# latch_THT.net
KiCad netlist of a schematic drawn in EAGLE
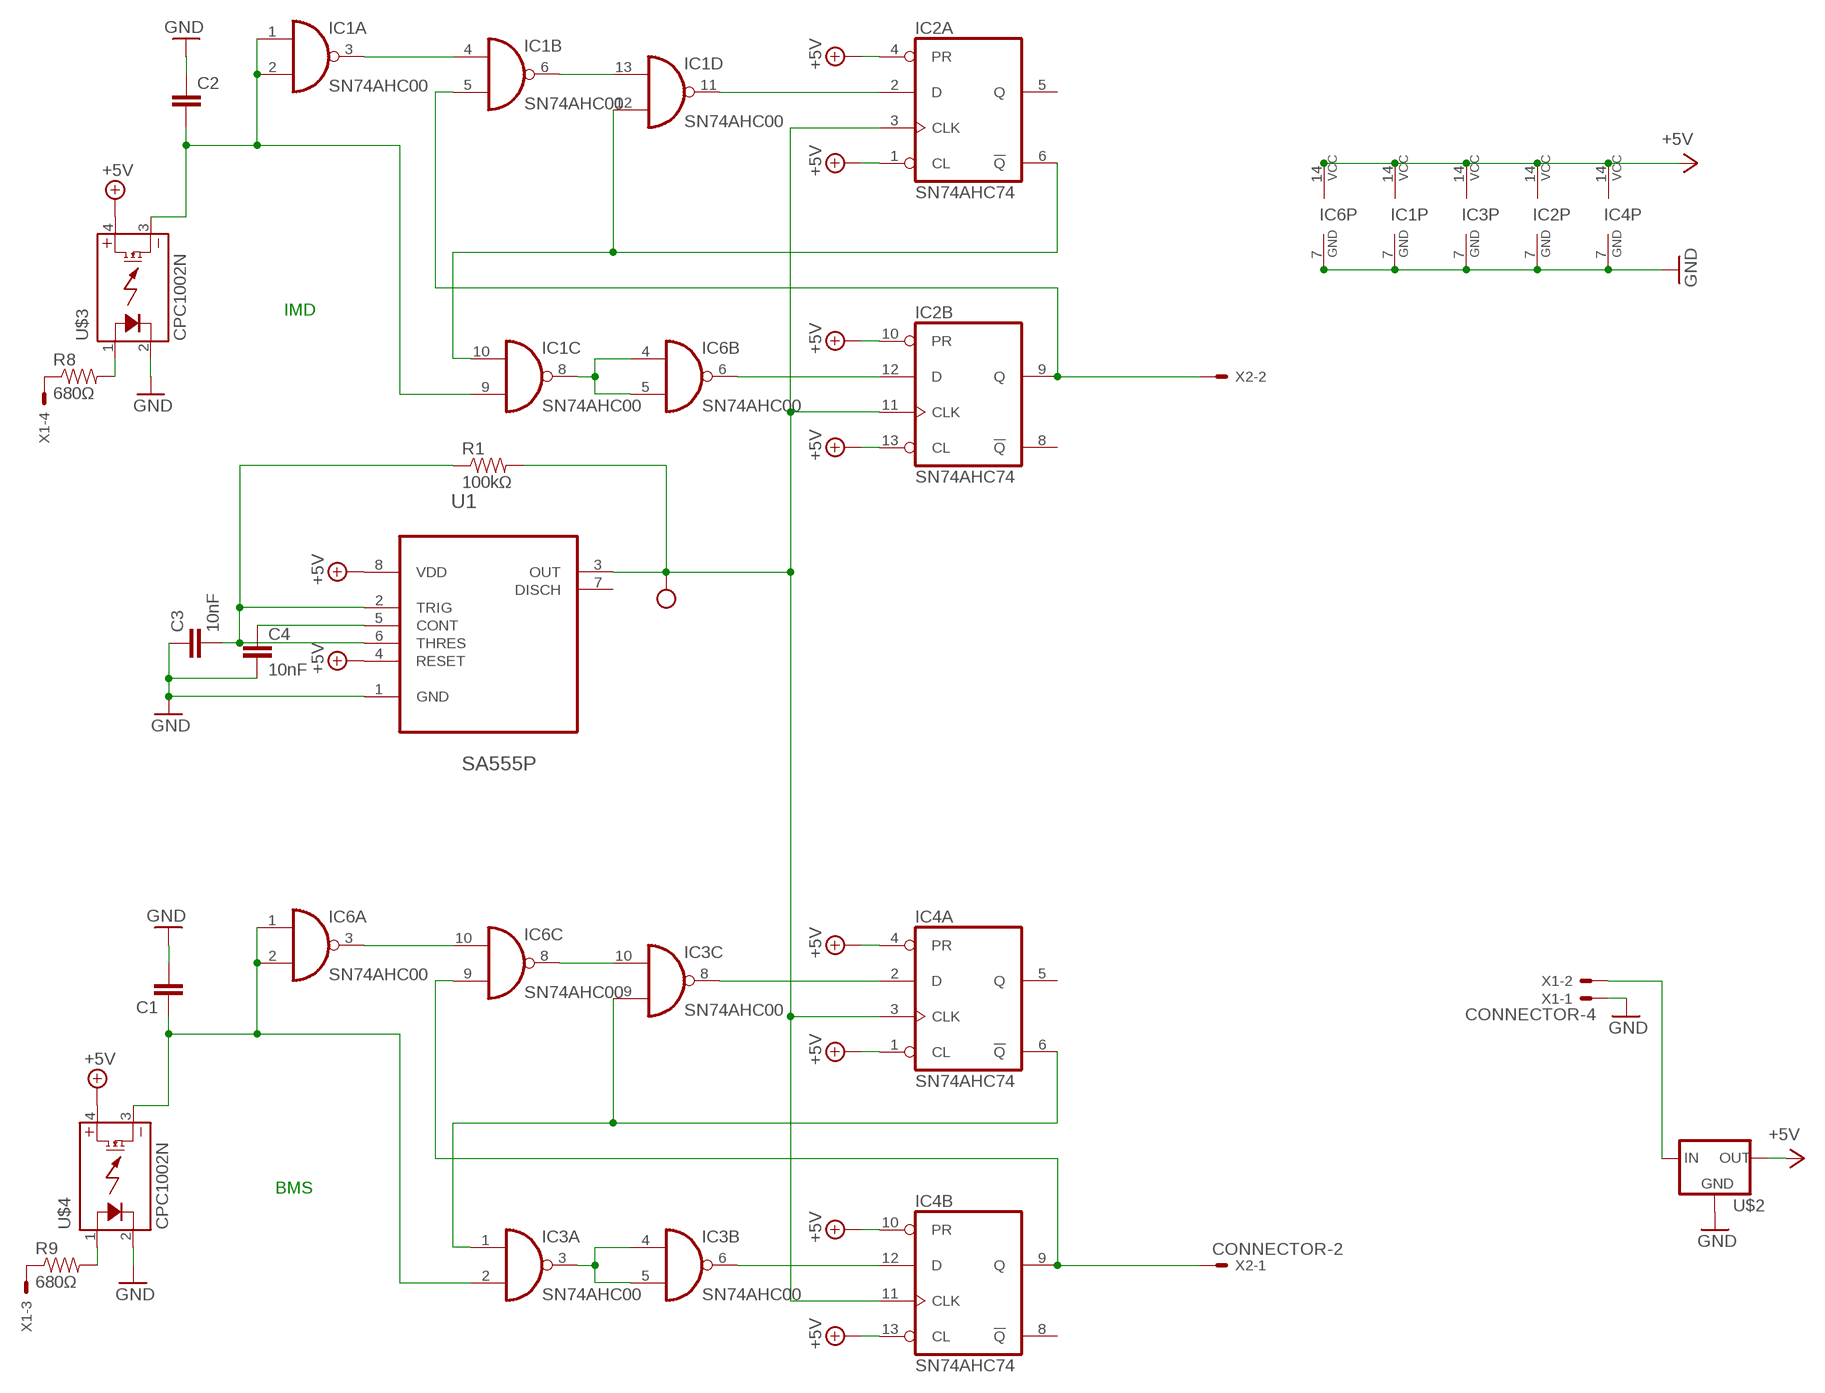
[diagram p0: schematic, sheet 1]

(export (version "E")
  (design (tool "Eeschema 10.0.6"))
  (components
    (comp (ref "C1")
      (value "CAP_")
      (footprint "eagle-import:AXIAL-5MM")
      (libsource (lib "eagle-import") (part "CAP_"))
    )
    (comp (ref "C2")
      (value "CAP_")
      (footprint "eagle-import:AXIAL-5MM")
      (libsource (lib "eagle-import") (part "CAP_"))
    )
    (comp (ref "C3")
      (value "10nF")
      (footprint "eagle-import:AXIAL-5MM")
      (libsource (lib "eagle-import") (part "CAP_"))
    )
    (comp (ref "C4")
      (value "10nF")
      (footprint "eagle-import:AXIAL-5MM")
      (libsource (lib "eagle-import") (part "CAP_"))
    )
    (comp (ref "IC1")
      (value "SN74AHC00")
      (footprint "eagle-import:DIL14")
      (libsource (lib "eagle-import") (part "SN74AHC00"))
    )
    (comp (ref "IC2")
      (value "SN74AHC74")
      (footprint "eagle-import:DIL14")
      (libsource (lib "eagle-import") (part "SN74AHC74"))
    )
    (comp (ref "IC3")
      (value "SN74AHC00")
      (footprint "eagle-import:DIL14")
      (libsource (lib "eagle-import") (part "SN74AHC00"))
    )
    (comp (ref "IC4")
      (value "SN74AHC74")
      (footprint "eagle-import:DIL14")
      (libsource (lib "eagle-import") (part "SN74AHC74"))
    )
    (comp (ref "IC6")
      (value "SN74AHC00")
      (footprint "eagle-import:DIL14")
      (libsource (lib "eagle-import") (part "SN74AHC00"))
    )
    (comp (ref "R1")
      (value "100kΩ")
      (footprint "eagle-import:AXIAL-0.4")
      (libsource (lib "eagle-import") (part "RESISTORPTH-1/4W"))
    )
    (comp (ref "R8")
      (value "680Ω")
      (footprint "eagle-import:AXIAL-0.4")
      (libsource (lib "eagle-import") (part "RESISTORPTH-1/4W"))
    )
    (comp (ref "R9")
      (value "680Ω")
      (footprint "eagle-import:AXIAL-0.4")
      (libsource (lib "eagle-import") (part "RESISTORPTH-1/4W"))
    )
    (comp (ref "U$1")
      (value "TEST_POINT")
      (footprint "eagle-import:TEST_POINT")
      (libsource (lib "eagle-import") (part "TEST_POINT"))
    )
    (comp (ref "U$2")
      (value "5VREG_LM340-NLM340T-5.0/NOPB")
      (footprint "eagle-import:TO-220")
      (libsource (lib "eagle-import") (part "5VREG_LM340-NLM340T-5.0/NOPB"))
    )
    (comp (ref "U$3")
      (value "CPC1002N")
      (footprint "eagle-import:SOP04")
      (libsource (lib "eagle-import") (part "CPC1002N"))
    )
    (comp (ref "U$4")
      (value "CPC1002N")
      (footprint "eagle-import:SOP04")
      (libsource (lib "eagle-import") (part "CPC1002N"))
    )
    (comp (ref "U1")
      (value "SA555P")
      (footprint "eagle-import:DIP254P762X508-8")
      (libsource (lib "eagle-import") (part "SA555P"))
    )
    (comp (ref "X1")
      (value "CONNECTOR-4")
      (footprint "eagle-import:MINIFIT_5566-4")
      (libsource (lib "eagle-import") (part "CONNECTOR-4"))
    )
    (comp (ref "X2")
      (value "CONNECTOR-2")
      (footprint "eagle-import:MINIFIT_5566-2")
      (libsource (lib "eagle-import") (part "CONNECTOR-2"))
    )
  )
  (nets
    (net (code "1") (name "+5V") (class "Default")
      (node (ref "IC1") (pin "14") (pinfunction "VCC_14") (pintype "power_in"))
      (node (ref "IC2") (pin "1") (pinfunction "CL_1") (pintype "input"))
      (node (ref "IC2") (pin "10") (pinfunction "PR_10") (pintype "input"))
      (node (ref "IC2") (pin "13") (pinfunction "CL_13") (pintype "input"))
      (node (ref "IC2") (pin "14") (pinfunction "VCC_14") (pintype "power_in"))
      (node (ref "IC2") (pin "4") (pinfunction "PR_4") (pintype "input"))
      (node (ref "IC3") (pin "14") (pinfunction "VCC_14") (pintype "power_in"))
      (node (ref "IC4") (pin "1") (pinfunction "CL_1") (pintype "input"))
      (node (ref "IC4") (pin "10") (pinfunction "PR_10") (pintype "input"))
      (node (ref "IC4") (pin "13") (pinfunction "CL_13") (pintype "input"))
      (node (ref "IC4") (pin "14") (pinfunction "VCC_14") (pintype "power_in"))
      (node (ref "IC4") (pin "4") (pinfunction "PR_4") (pintype "input"))
      (node (ref "IC6") (pin "14") (pinfunction "VCC_14") (pintype "power_in"))
      (node (ref "U$2") (pin "3") (pinfunction "OUT_3") (pintype "output"))
      (node (ref "U$3") (pin "4") (pinfunction "DC+_4") (pintype "passive"))
      (node (ref "U$4") (pin "4") (pinfunction "DC+_4") (pintype "passive"))
      (node (ref "U1") (pin "4") (pinfunction "RESET_4") (pintype "input"))
      (node (ref "U1") (pin "8") (pinfunction "VDD_8") (pintype "power_in"))
    )
    (net (code "2") (name "GND") (class "Default")
      (node (ref "C1") (pin "P$2") (pinfunction "2_P$2") (pintype "passive"))
      (node (ref "C2") (pin "P$1") (pinfunction "1_P$1") (pintype "passive"))
      (node (ref "C3") (pin "P$1") (pinfunction "1_P$1") (pintype "passive"))
      (node (ref "C4") (pin "P$2") (pinfunction "2_P$2") (pintype "passive"))
      (node (ref "IC1") (pin "7") (pinfunction "GND_7") (pintype "power_in"))
      (node (ref "IC2") (pin "7") (pinfunction "GND_7") (pintype "power_in"))
      (node (ref "IC3") (pin "7") (pinfunction "GND_7") (pintype "power_in"))
      (node (ref "IC4") (pin "7") (pinfunction "GND_7") (pintype "power_in"))
      (node (ref "IC6") (pin "7") (pinfunction "GND_7") (pintype "power_in"))
      (node (ref "U$2") (pin "2") (pinfunction "GND_2") (pintype "input"))
      (node (ref "U$3") (pin "2") (pinfunction "CONTROL-_2") (pintype "passive"))
      (node (ref "U$4") (pin "2") (pinfunction "CONTROL-_2") (pintype "passive"))
      (node (ref "U1") (pin "1") (pinfunction "GND_1") (pintype "passive"))
      (node (ref "X1") (pin "1") (pinfunction "S_1") (pintype "passive"))
    )
    (net (code "3") (name "Net-(C1-1)") (class "Default")
      (node (ref "C1") (pin "P$1") (pinfunction "1_P$1") (pintype "passive"))
      (node (ref "IC3") (pin "2") (pinfunction "I1_2") (pintype "input"))
      (node (ref "IC6") (pin "1") (pinfunction "I0_1") (pintype "input"))
      (node (ref "IC6") (pin "2") (pinfunction "I1_2") (pintype "input"))
      (node (ref "U$4") (pin "3") (pinfunction "DC-_3") (pintype "passive"))
    )
    (net (code "4") (name "Net-(C2-2)") (class "Default")
      (node (ref "C2") (pin "P$2") (pinfunction "2_P$2") (pintype "passive"))
      (node (ref "IC1") (pin "1") (pinfunction "I0_1") (pintype "input"))
      (node (ref "IC1") (pin "2") (pinfunction "I1_2") (pintype "input"))
      (node (ref "IC1") (pin "9") (pinfunction "I1_9") (pintype "input"))
      (node (ref "U$3") (pin "3") (pinfunction "DC-_3") (pintype "passive"))
    )
    (net (code "5") (name "Net-(C3-2)") (class "Default")
      (node (ref "C3") (pin "P$2") (pinfunction "2_P$2") (pintype "passive"))
      (node (ref "R1") (pin "P$1") (pinfunction "1_P$1") (pintype "passive"))
      (node (ref "U1") (pin "2") (pinfunction "TRIG_2") (pintype "input"))
      (node (ref "U1") (pin "6") (pinfunction "THRES_6") (pintype "input"))
    )
    (net (code "6") (name "Net-(C4-1)") (class "Default")
      (node (ref "C4") (pin "P$1") (pinfunction "1_P$1") (pintype "passive"))
      (node (ref "U1") (pin "5") (pinfunction "CONT_5") (pintype "input"))
    )
    (net (code "7") (name "Net-(IC1A-O)") (class "Default")
      (node (ref "IC1") (pin "3") (pinfunction "O_3") (pintype "output"))
      (node (ref "IC1") (pin "4") (pinfunction "I0_4") (pintype "input"))
    )
    (net (code "8") (name "Net-(IC1B-I1)") (class "Default")
      (node (ref "IC1") (pin "5") (pinfunction "I1_5") (pintype "input"))
      (node (ref "IC2") (pin "9") (pinfunction "Q_9") (pintype "output"))
      (node (ref "X2") (pin "2") (pinfunction "S_2") (pintype "passive"))
    )
    (net (code "9") (name "Net-(IC1B-O)") (class "Default")
      (node (ref "IC1") (pin "13") (pinfunction "I0_13") (pintype "input"))
      (node (ref "IC1") (pin "6") (pinfunction "O_6") (pintype "output"))
    )
    (net (code "10") (name "Net-(IC1C-I0)") (class "Default")
      (node (ref "IC1") (pin "10") (pinfunction "I0_10") (pintype "input"))
      (node (ref "IC1") (pin "12") (pinfunction "I1_12") (pintype "input"))
      (node (ref "IC2") (pin "6") (pinfunction "~{Q}_6") (pintype "output"))
    )
    (net (code "11") (name "Net-(IC1C-O)") (class "Default")
      (node (ref "IC1") (pin "8") (pinfunction "O_8") (pintype "output"))
      (node (ref "IC6") (pin "4") (pinfunction "I0_4") (pintype "input"))
      (node (ref "IC6") (pin "5") (pinfunction "I1_5") (pintype "input"))
    )
    (net (code "12") (name "Net-(IC1D-O)") (class "Default")
      (node (ref "IC1") (pin "11") (pinfunction "O_11") (pintype "output"))
      (node (ref "IC2") (pin "2") (pinfunction "D_2") (pintype "input"))
    )
    (net (code "13") (name "Net-(IC2A-CLK)") (class "Default")
      (node (ref "IC2") (pin "11") (pinfunction "CLK_11") (pintype "input"))
      (node (ref "IC2") (pin "3") (pinfunction "CLK_3") (pintype "input"))
      (node (ref "IC4") (pin "11") (pinfunction "CLK_11") (pintype "input"))
      (node (ref "IC4") (pin "3") (pinfunction "CLK_3") (pintype "input"))
      (node (ref "R1") (pin "P$2") (pinfunction "2_P$2") (pintype "passive"))
      (node (ref "U$1") (pin "P$1") (pinfunction "P$1_P$1") (pintype "bidirectional"))
      (node (ref "U1") (pin "3") (pinfunction "OUT_3") (pintype "output"))
    )
    (net (code "14") (name "Net-(IC2B-D)") (class "Default")
      (node (ref "IC2") (pin "12") (pinfunction "D_12") (pintype "input"))
      (node (ref "IC6") (pin "6") (pinfunction "O_6") (pintype "output"))
    )
    (net (code "15") (name "Net-(IC3A-I0)") (class "Default")
      (node (ref "IC3") (pin "1") (pinfunction "I0_1") (pintype "input"))
      (node (ref "IC3") (pin "9") (pinfunction "I1_9") (pintype "input"))
      (node (ref "IC4") (pin "6") (pinfunction "~{Q}_6") (pintype "output"))
    )
    (net (code "16") (name "Net-(IC3A-O)") (class "Default")
      (node (ref "IC3") (pin "3") (pinfunction "O_3") (pintype "output"))
      (node (ref "IC3") (pin "4") (pinfunction "I0_4") (pintype "input"))
      (node (ref "IC3") (pin "5") (pinfunction "I1_5") (pintype "input"))
    )
    (net (code "17") (name "Net-(IC3B-O)") (class "Default")
      (node (ref "IC3") (pin "6") (pinfunction "O_6") (pintype "output"))
      (node (ref "IC4") (pin "12") (pinfunction "D_12") (pintype "input"))
    )
    (net (code "18") (name "Net-(IC3C-I0)") (class "Default")
      (node (ref "IC3") (pin "10") (pinfunction "I0_10") (pintype "input"))
      (node (ref "IC6") (pin "8") (pinfunction "O_8") (pintype "output"))
    )
    (net (code "19") (name "Net-(IC3C-O)") (class "Default")
      (node (ref "IC3") (pin "8") (pinfunction "O_8") (pintype "output"))
      (node (ref "IC4") (pin "2") (pinfunction "D_2") (pintype "input"))
    )
    (net (code "20") (name "Net-(IC4B-Q)") (class "Default")
      (node (ref "IC4") (pin "9") (pinfunction "Q_9") (pintype "output"))
      (node (ref "IC6") (pin "9") (pinfunction "I1_9") (pintype "input"))
      (node (ref "X2") (pin "1") (pinfunction "S_1") (pintype "passive"))
    )
    (net (code "21") (name "Net-(IC6A-O)") (class "Default")
      (node (ref "IC6") (pin "10") (pinfunction "I0_10") (pintype "input"))
      (node (ref "IC6") (pin "3") (pinfunction "O_3") (pintype "output"))
    )
    (net (code "22") (name "Net-(R8-1)") (class "Default")
      (node (ref "R8") (pin "P$1") (pinfunction "1_P$1") (pintype "passive"))
      (node (ref "X1") (pin "4") (pinfunction "S_4") (pintype "passive"))
    )
    (net (code "23") (name "Net-(R8-2)") (class "Default")
      (node (ref "R8") (pin "P$2") (pinfunction "2_P$2") (pintype "passive"))
      (node (ref "U$3") (pin "1") (pinfunction "CONTROL+_1") (pintype "passive"))
    )
    (net (code "24") (name "Net-(R9-1)") (class "Default")
      (node (ref "R9") (pin "P$1") (pinfunction "1_P$1") (pintype "passive"))
      (node (ref "X1") (pin "3") (pinfunction "S_3") (pintype "passive"))
    )
    (net (code "25") (name "Net-(R9-2)") (class "Default")
      (node (ref "R9") (pin "P$2") (pinfunction "2_P$2") (pintype "passive"))
      (node (ref "U$4") (pin "1") (pinfunction "CONTROL+_1") (pintype "passive"))
    )
    (net (code "26") (name "Net-(U$2-IN)") (class "Default")
      (node (ref "U$2") (pin "1") (pinfunction "IN_1") (pintype "input"))
      (node (ref "X1") (pin "2") (pinfunction "S_2") (pintype "passive"))
    )
    (net (code "27") (name "unconnected-(IC2A-Q-Pad5)") (class "Default")
      (node (ref "IC2") (pin "5") (pinfunction "Q_5") (pintype "output"))
    )
    (net (code "28") (name "unconnected-(IC2B-~{Q}-Pad8)") (class "Default")
      (node (ref "IC2") (pin "8") (pinfunction "~{Q}_8") (pintype "output"))
    )
    (net (code "29") (name "unconnected-(IC4A-Q-Pad5)") (class "Default")
      (node (ref "IC4") (pin "5") (pinfunction "Q_5") (pintype "output"))
    )
    (net (code "30") (name "unconnected-(IC4B-~{Q}-Pad8)") (class "Default")
      (node (ref "IC4") (pin "8") (pinfunction "~{Q}_8") (pintype "output"))
    )
    (net (code "31") (name "unconnected-(U1-DISCH-Pad7)") (class "Default")
      (node (ref "U1") (pin "7") (pinfunction "DISCH_7") (pintype "output"))
    )
  )
)
